# main.net
KiCad netlist of a schematic drawn in Altium Designer
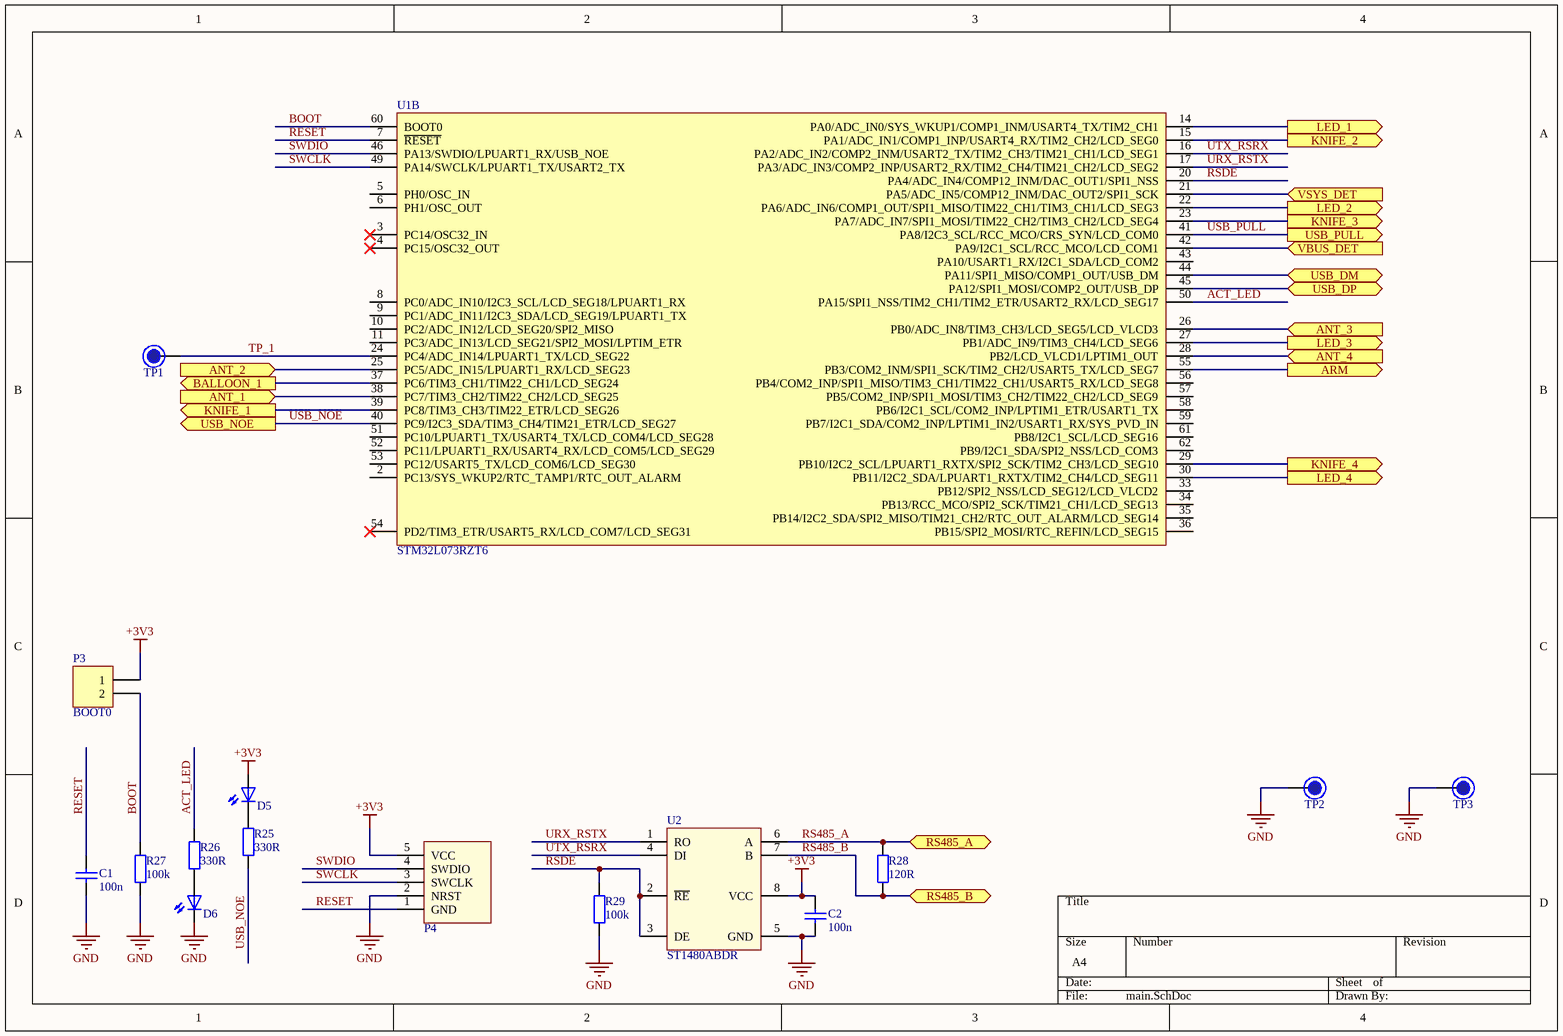
[diagram p0: main.SchDoc]

(export (version "E")
  (design (tool "Eeschema 10.0.6"))
  (components
    (comp (ref "C1")
      (value "100n")
      (footprint "C0603_IPC_MD")
      (description "CAP CER 0.1UF 16V X7R 0603")
      (fields
        (field (name "MANUFACTURER") "Samsung Electro-Mechanics")
        (field (name "MANUFACTURER PART NUMBER") "CL10B104KO8NNNC")
      )
      (libsource (lib "alfasat_lib") (part "CL10B104KO8NNNC"))
    )
    (comp (ref "C2")
      (value "100n")
      (footprint "C0603_IPC_MD")
      (description "CAP CER 0.1UF 16V X7R 0603")
      (fields
        (field (name "MANUFACTURER") "Samsung Electro-Mechanics")
        (field (name "MANUFACTURER PART NUMBER") "CL10B104KO8NNNC")
      )
      (libsource (lib "alfasat_lib") (part "CL10B104KO8NNNC"))
    )
    (comp (ref "D5")
      (value "LTST-C190GKT")
      (footprint "LED_0603")
      (description "LED GREEN CLEAR CHIP SMD 0603")
      (fields (field (name "MANUFACTURER") "Lite-On Inc."))
      (libsource (lib "alfasat_parts_lib") (part "LTST-C190GKT"))
    )
    (comp (ref "D6")
      (value "LTST-C190GKT")
      (footprint "LED_0603")
      (description "LED GREEN CLEAR CHIP SMD 0603")
      (fields (field (name "MANUFACTURER") "Lite-On Inc."))
      (libsource (lib "alfasat_lib") (part "LTST-C190GKT"))
    )
    (comp (ref "P3")
      (value "BOOT0")
      (footprint "HDR1X2")
      (description "Header, 2-Pin")
      (fields (field (name "PUBLISHER") "Altium Limited"))
      (libsource (lib "Miscellaneous Connectors") (part "Header 2"))
    )
    (comp (ref "P4")
      (value "SWD")
      (footprint "SWD_CON_VAR2")
      (description "SWDIO SWCLK VDD GND NRST")
      (libsource (lib "alfasat_lib") (part "SWD-CONNECTOR_VAR1"))
    )
    (comp (ref "R25")
      (value "330R")
      (footprint "R0603_IPC_MD")
      (description "RES SMD 330 OHM 5% 1/10W 0603")
      (fields
        (field (name "MANUFACTURER") "Bourns Inc.")
        (field (name "MANUFACTURER PART NUMBER") "CR0603-JW-331ELF")
      )
      (libsource (lib "alfasat_parts_lib") (part "CR0603-JW-331ELF"))
    )
    (comp (ref "R26")
      (value "330R")
      (footprint "R0603_IPC_MD")
      (description "RES SMD 330 OHM 5% 1/10W 0603")
      (fields
        (field (name "MANUFACTURER") "Bourns Inc.")
        (field (name "MANUFACTURER PART NUMBER") "CR0603-JW-331ELF")
      )
      (libsource (lib "alfasat_lib") (part "CR0603-JW-331ELF"))
    )
    (comp (ref "R27")
      (value "100k")
      (footprint "R0603_IPC_MD")
      (description "RES 100K OHM 1% 1/10W 0603")
      (fields
        (field (name "MANUFACTURER") "Bourns Inc.")
        (field (name "MANUFACTURER PART NUMBER") "RMCF0603FT100K")
      )
      (libsource (lib "alfasat_lib") (part "RMCF0603FT100K"))
    )
    (comp (ref "R28")
      (value "120R")
      (footprint "R0603_IPC_MD")
      (description "RES SMD 120 OHM 5% 1/10W 0603")
      (fields
        (field (name "MANUFACTURER") "Yageo")
        (field (name "MANUFACTURER PART NUMBER") "RC0603JR-07120RL")
      )
      (libsource (lib "alfasat_lib") (part "RC0603JR-07120RL"))
    )
    (comp (ref "R29")
      (value "100k")
      (footprint "R0603_IPC_MD")
      (description "RES 100K OHM 1% 1/10W 0603")
      (fields
        (field (name "MANUFACTURER") "Bourns Inc.")
        (field (name "MANUFACTURER PART NUMBER") "RMCF0603FT100K")
      )
      (libsource (lib "alfasat_lib") (part "RMCF0603FT100K"))
    )
    (comp (ref "TP1")
      (value "Test Point")
      (footprint "TestPoint_1M5")
      (libsource (lib "alfasat_parts_lib") (part "TP"))
    )
    (comp (ref "TP2")
      (value "GND")
      (footprint "TestPoint_1M5_TH")
      (description "Test Point")
      (libsource (lib "alfasat_parts_lib") (part "TP"))
    )
    (comp (ref "TP3")
      (value "GND")
      (footprint "TestPoint_1M5_TH")
      (description "Test Point")
      (libsource (lib "alfasat_parts_lib") (part "TP"))
    )
    (comp (ref "U1")
      (value "STM32L073RZT6")
      (footprint "LQFP64_10X10MM")
      (description "Ultra-low-power 32-bit MCU ARM®-based Cortex®-M0+")
      (fields (field (name "MANUFACTURER") "ST"))
      (libsource (lib "alfasat_parts_lib") (part "STM32L073RZT6"))
    )
    (comp (ref "U2")
      (value "ST1480ABDR")
      (footprint "SOIC-8")
      (description "IC TXRX 3.3V RS485/422 8 SOIC")
      (fields (field (name "MANUFACTURER") "STMicroelectronics"))
      (libsource (lib "alfasat_lib") (part "ST1480ABDR"))
    )
  )
  (nets
    (net (code "1") (name "+3V3") (class "Default")
      (node (ref "C2") (pin "2") (pinfunction "2_2") (pintype "passive"))
      (node (ref "D5") (pin "2") (pinfunction "A_2") (pintype "passive"))
      (node (ref "P3") (pin "1") (pinfunction "1_1") (pintype "passive"))
      (node (ref "P4") (pin "5") (pinfunction "VCC_5") (pintype "passive"))
      (node (ref "U2") (pin "8") (pinfunction "VCC_8") (pintype "passive"))
    )
    (net (code "2") (name "/ACT_LED") (class "Default")
      (node (ref "R26") (pin "1") (pinfunction "1_1") (pintype "passive"))
      (node (ref "U1") (pin "50") (pinfunction "PA15/SPI1_NSS/TIM2_CH1/TIM2_ETR/USART2_RX/LCD_SEG17_50") (pintype "passive"))
    )
    (net (code "3") (name "/ANT_1") (class "Default")
      (node (ref "U1") (pin "38") (pinfunction "PC7/TIM3_CH2/TIM22_CH2/LCD_SEG25_38") (pintype "passive"))
    )
    (net (code "4") (name "/ANT_2") (class "Default")
      (node (ref "U1") (pin "25") (pinfunction "PC5/ADC_IN15/LPUART1_RX/LCD_SEG23_25") (pintype "passive"))
    )
    (net (code "5") (name "/ANT_3") (class "Default")
      (node (ref "U1") (pin "26") (pinfunction "PB0/ADC_IN8/TIM3_CH3/LCD_SEG5/LCD_VLCD3_26") (pintype "passive"))
    )
    (net (code "6") (name "/ANT_4") (class "Default")
      (node (ref "U1") (pin "28") (pinfunction "PB2/LCD_VLCD1/LPTIM1_OUT_28") (pintype "passive"))
    )
    (net (code "7") (name "/ARM") (class "Default")
      (node (ref "U1") (pin "55") (pinfunction "PB3/COM2_INM/SPI1_SCK/TIM2_CH2/USART5_TX/LCD_SEG7_55") (pintype "passive"))
    )
    (net (code "8") (name "/BALLOON_1") (class "Default")
      (node (ref "U1") (pin "37") (pinfunction "PC6/TIM3_CH1/TIM22_CH1/LCD_SEG24_37") (pintype "passive"))
    )
    (net (code "9") (name "/BOOT") (class "Default")
      (node (ref "P3") (pin "2") (pinfunction "2_2") (pintype "passive"))
      (node (ref "R27") (pin "2") (pinfunction "2_2") (pintype "passive"))
      (node (ref "U1") (pin "60") (pinfunction "BOOT0_60") (pintype "passive"))
    )
    (net (code "10") (name "/KNIFE_1") (class "Default")
      (node (ref "U1") (pin "39") (pinfunction "PC8/TIM3_CH3/TIM22_ETR/LCD_SEG26_39") (pintype "passive"))
    )
    (net (code "11") (name "/KNIFE_2") (class "Default")
      (node (ref "U1") (pin "15") (pinfunction "PA1/ADC_IN1/COMP1_INP/USART4_RX/TIM2_CH2/LCD_SEG0_15") (pintype "passive"))
    )
    (net (code "12") (name "/KNIFE_3") (class "Default")
      (node (ref "U1") (pin "23") (pinfunction "PA7/ADC_IN7/SPI1_MOSI/TIM22_CH2/TIM3_CH2/LCD_SEG4_23") (pintype "passive"))
    )
    (net (code "13") (name "/KNIFE_4") (class "Default")
      (node (ref "U1") (pin "29") (pinfunction "PB10/I2C2_SCL/LPUART1_RXTX/SPI2_SCK/TIM2_CH3/LCD_SEG10_29") (pintype "passive"))
    )
    (net (code "14") (name "/LED_1") (class "Default")
      (node (ref "U1") (pin "14") (pinfunction "PA0/ADC_IN0/SYS_WKUP1/COMP1_INM/USART4_TX/TIM2_CH1_14") (pintype "passive"))
    )
    (net (code "15") (name "/LED_2") (class "Default")
      (node (ref "U1") (pin "22") (pinfunction "PA6/ADC_IN6/COMP1_OUT/SPI1_MISO/TIM22_CH1/TIM3_CH1/LCD_SEG3_22") (pintype "passive"))
    )
    (net (code "16") (name "/LED_3") (class "Default")
      (node (ref "U1") (pin "27") (pinfunction "PB1/ADC_IN9/TIM3_CH4/LCD_SEG6_27") (pintype "passive"))
    )
    (net (code "17") (name "/LED_4") (class "Default")
      (node (ref "U1") (pin "30") (pinfunction "PB11/I2C2_SDA/LPUART1_RXTX/TIM2_CH4/LCD_SEG11_30") (pintype "passive"))
    )
    (net (code "18") (name "/RESET") (class "Default")
      (node (ref "C1") (pin "2") (pinfunction "2_2") (pintype "passive"))
      (node (ref "P4") (pin "1") (pinfunction "GND_1") (pintype "passive"))
      (node (ref "U1") (pin "7") (pinfunction "~{RESET}_7") (pintype "passive"))
    )
    (net (code "19") (name "/RS485_A") (class "Default")
      (node (ref "R28") (pin "2") (pinfunction "2_2") (pintype "passive"))
      (node (ref "U2") (pin "6") (pinfunction "A_6") (pintype "passive"))
    )
    (net (code "20") (name "/RS485_B") (class "Default")
      (node (ref "R28") (pin "1") (pinfunction "1_1") (pintype "passive"))
      (node (ref "U2") (pin "7") (pinfunction "B_7") (pintype "passive"))
    )
    (net (code "21") (name "/RSDE") (class "Default")
      (node (ref "R29") (pin "2") (pinfunction "2_2") (pintype "passive"))
      (node (ref "U1") (pin "20") (pinfunction "PA4/ADC_IN4/COMP12_INM/DAC_OUT1/SPI1_NSS_20") (pintype "passive"))
      (node (ref "U2") (pin "2") (pinfunction "~{RE}_2") (pintype "passive"))
      (node (ref "U2") (pin "3") (pinfunction "DE_3") (pintype "passive"))
    )
    (net (code "22") (name "/SWCLK") (class "Default")
      (node (ref "P4") (pin "3") (pinfunction "SWCLK_3") (pintype "passive"))
      (node (ref "U1") (pin "49") (pinfunction "PA14/SWCLK/LPUART1_TX/USART2_TX_49") (pintype "passive"))
    )
    (net (code "23") (name "/SWDIO") (class "Default")
      (node (ref "P4") (pin "4") (pinfunction "SWDIO_4") (pintype "passive"))
      (node (ref "U1") (pin "46") (pinfunction "PA13/SWDIO/LPUART1_RX/USB_NOE_46") (pintype "passive"))
    )
    (net (code "24") (name "/TP_1") (class "Default")
      (node (ref "TP1") (pin "0") (pinfunction "0_0") (pintype "passive"))
      (node (ref "U1") (pin "24") (pinfunction "PC4/ADC_IN14/LPUART1_TX/LCD_SEG22_24") (pintype "passive"))
    )
    (net (code "25") (name "/URX_RSTX") (class "Default")
      (node (ref "U1") (pin "17") (pinfunction "PA3/ADC_IN3/COMP2_INP/USART2_RX/TIM2_CH4/TIM21_CH2/LCD_SEG2_17") (pintype "passive"))
      (node (ref "U2") (pin "1") (pinfunction "RO_1") (pintype "passive"))
    )
    (net (code "26") (name "/USB_DM") (class "Default")
      (node (ref "U1") (pin "44") (pinfunction "PA11/SPI1_MISO/COMP1_OUT/USB_DM_44") (pintype "passive"))
    )
    (net (code "27") (name "/USB_DP") (class "Default")
      (node (ref "U1") (pin "45") (pinfunction "PA12/SPI1_MOSI/COMP2_OUT/USB_DP_45") (pintype "passive"))
    )
    (net (code "28") (name "/USB_NOE") (class "Default")
      (node (ref "R25") (pin "2") (pinfunction "2_2") (pintype "passive"))
      (node (ref "U1") (pin "40") (pinfunction "PC9/I2C3_SDA/TIM3_CH4/TIM21_ETR/LCD_SEG27_40") (pintype "passive"))
    )
    (net (code "29") (name "/USB_PULL") (class "Default")
      (node (ref "U1") (pin "41") (pinfunction "PA8/I2C3_SCL/RCC_MCO/CRS_SYN/LCD_COM0_41") (pintype "passive"))
    )
    (net (code "30") (name "/UTX_RSRX") (class "Default")
      (node (ref "U1") (pin "16") (pinfunction "PA2/ADC_IN2/COMP2_INM/USART2_TX/TIM2_CH3/TIM21_CH1/LCD_SEG1_16") (pintype "passive"))
      (node (ref "U2") (pin "4") (pinfunction "DI_4") (pintype "passive"))
    )
    (net (code "31") (name "/VBUS_DET") (class "Default")
      (node (ref "U1") (pin "42") (pinfunction "PA9/I2C1_SCL/RCC_MCO/LCD_COM1_42") (pintype "passive"))
    )
    (net (code "32") (name "/VSYS_DET") (class "Default")
      (node (ref "U1") (pin "21") (pinfunction "PA5/ADC_IN5/COMP12_INM/DAC_OUT2/SPI1_SCK_21") (pintype "passive"))
    )
    (net (code "33") (name "GND") (class "Default")
      (node (ref "C1") (pin "1") (pinfunction "1_1") (pintype "passive"))
      (node (ref "C2") (pin "1") (pinfunction "1_1") (pintype "passive"))
      (node (ref "D6") (pin "1") (pinfunction "C_1") (pintype "passive"))
      (node (ref "P4") (pin "2") (pinfunction "NRST_2") (pintype "passive"))
      (node (ref "R27") (pin "1") (pinfunction "1_1") (pintype "passive"))
      (node (ref "R29") (pin "1") (pinfunction "1_1") (pintype "passive"))
      (node (ref "TP2") (pin "0") (pinfunction "0_0") (pintype "passive"))
      (node (ref "TP3") (pin "0") (pinfunction "0_0") (pintype "passive"))
      (node (ref "U2") (pin "5") (pinfunction "GND_5") (pintype "passive"))
    )
    (net (code "34") (name "Net-(D5-C)") (class "Default")
      (node (ref "D5") (pin "1") (pinfunction "C_1") (pintype "passive"))
      (node (ref "R25") (pin "1") (pinfunction "1_1") (pintype "passive"))
    )
    (net (code "35") (name "Net-(D6-A)") (class "Default")
      (node (ref "D6") (pin "2") (pinfunction "A_2") (pintype "passive"))
      (node (ref "R26") (pin "2") (pinfunction "2_2") (pintype "passive"))
    )
    (net (code "36") (name "unconnected-(U1B-PA10{slash}USART1_RX{slash}I2C1_SDA{slash}LCD_COM2-Pad43)") (class "Default")
      (node (ref "U1") (pin "43") (pinfunction "PA10/USART1_RX/I2C1_SDA/LCD_COM2_43") (pintype "passive"))
    )
    (net (code "37") (name "unconnected-(U1B-PB4{slash}COM2_INP{slash}SPI1_MISO{slash}TIM3_CH1{slash}TIM22_CH1{slash}USART5_RX{slash}LCD_SEG8-Pad56)") (class "Default")
      (node (ref "U1") (pin "56") (pinfunction "PB4/COM2_INP/SPI1_MISO/TIM3_CH1/TIM22_CH1/USART5_RX/LCD_SEG8_56") (pintype "passive"))
    )
    (net (code "38") (name "unconnected-(U1B-PB5{slash}COM2_INP{slash}SPI1_MOSI{slash}TIM3_CH2{slash}TIM22_CH2{slash}LCD_SEG9-Pad57)") (class "Default")
      (node (ref "U1") (pin "57") (pinfunction "PB5/COM2_INP/SPI1_MOSI/TIM3_CH2/TIM22_CH2/LCD_SEG9_57") (pintype "passive"))
    )
    (net (code "39") (name "unconnected-(U1B-PB6{slash}I2C1_SCL{slash}COM2_INP{slash}LPTIM1_ETR{slash}USART1_TX-Pad58)") (class "Default")
      (node (ref "U1") (pin "58") (pinfunction "PB6/I2C1_SCL/COM2_INP/LPTIM1_ETR/USART1_TX_58") (pintype "passive"))
    )
    (net (code "40") (name "unconnected-(U1B-PB7{slash}I2C1_SDA{slash}COM2_INP{slash}LPTIM1_IN2{slash}USART1_RX{slash}SYS_PVD_IN-Pad59)") (class "Default")
      (node (ref "U1") (pin "59") (pinfunction "PB7/I2C1_SDA/COM2_INP/LPTIM1_IN2/USART1_RX/SYS_PVD_IN_59") (pintype "passive"))
    )
    (net (code "41") (name "unconnected-(U1B-PB8{slash}I2C1_SCL{slash}LCD_SEG16-Pad61)") (class "Default")
      (node (ref "U1") (pin "61") (pinfunction "PB8/I2C1_SCL/LCD_SEG16_61") (pintype "passive"))
    )
    (net (code "42") (name "unconnected-(U1B-PB9{slash}I2C1_SDA{slash}SPI2_NSS{slash}LCD_COM3-Pad62)") (class "Default")
      (node (ref "U1") (pin "62") (pinfunction "PB9/I2C1_SDA/SPI2_NSS/LCD_COM3_62") (pintype "passive"))
    )
    (net (code "43") (name "unconnected-(U1B-PB12{slash}SPI2_NSS{slash}LCD_SEG12{slash}LCD_VLCD2-Pad33)") (class "Default")
      (node (ref "U1") (pin "33") (pinfunction "PB12/SPI2_NSS/LCD_SEG12/LCD_VLCD2_33") (pintype "passive"))
    )
    (net (code "44") (name "unconnected-(U1B-PB13{slash}RCC_MCO{slash}SPI2_SCK{slash}TIM21_CH1{slash}LCD_SEG13-Pad34)") (class "Default")
      (node (ref "U1") (pin "34") (pinfunction "PB13/RCC_MCO/SPI2_SCK/TIM21_CH1/LCD_SEG13_34") (pintype "passive"))
    )
    (net (code "45") (name "unconnected-(U1B-PB14{slash}I2C2_SDA{slash}SPI2_MISO{slash}TIM21_CH2{slash}RTC_OUT_ALARM{slash}LCD_SEG14-Pad35)") (class "Default")
      (node (ref "U1") (pin "35") (pinfunction "PB14/I2C2_SDA/SPI2_MISO/TIM21_CH2/RTC_OUT_ALARM/LCD_SEG14_35") (pintype "passive"))
    )
    (net (code "46") (name "unconnected-(U1B-PB15{slash}SPI2_MOSI{slash}RTC_REFIN{slash}LCD_SEG15-Pad36)") (class "Default")
      (node (ref "U1") (pin "36") (pinfunction "PB15/SPI2_MOSI/RTC_REFIN/LCD_SEG15_36") (pintype "passive"))
    )
    (net (code "47") (name "unconnected-(U1B-PC0{slash}ADC_IN10{slash}I2C3_SCL{slash}LCD_SEG18{slash}LPUART1_RX-Pad8)") (class "Default")
      (node (ref "U1") (pin "8") (pinfunction "PC0/ADC_IN10/I2C3_SCL/LCD_SEG18/LPUART1_RX_8") (pintype "passive"))
    )
    (net (code "48") (name "unconnected-(U1B-PC1{slash}ADC_IN11{slash}I2C3_SDA{slash}LCD_SEG19{slash}LPUART1_TX-Pad9)") (class "Default")
      (node (ref "U1") (pin "9") (pinfunction "PC1/ADC_IN11/I2C3_SDA/LCD_SEG19/LPUART1_TX_9") (pintype "passive"))
    )
    (net (code "49") (name "unconnected-(U1B-PC2{slash}ADC_IN12{slash}LCD_SEG20{slash}SPI2_MISO-Pad10)") (class "Default")
      (node (ref "U1") (pin "10") (pinfunction "PC2/ADC_IN12/LCD_SEG20/SPI2_MISO_10") (pintype "passive"))
    )
    (net (code "50") (name "unconnected-(U1B-PC3{slash}ADC_IN13{slash}LCD_SEG21{slash}SPI2_MOSI{slash}LPTIM_ETR-Pad11)") (class "Default")
      (node (ref "U1") (pin "11") (pinfunction "PC3/ADC_IN13/LCD_SEG21/SPI2_MOSI/LPTIM_ETR_11") (pintype "passive"))
    )
    (net (code "51") (name "unconnected-(U1B-PC10{slash}LPUART1_TX{slash}USART4_TX{slash}LCD_COM4{slash}LCD_SEG28-Pad51)") (class "Default")
      (node (ref "U1") (pin "51") (pinfunction "PC10/LPUART1_TX/USART4_TX/LCD_COM4/LCD_SEG28_51") (pintype "passive"))
    )
    (net (code "52") (name "unconnected-(U1B-PC11{slash}LPUART1_RX{slash}USART4_RX{slash}LCD_COM5{slash}LCD_SEG29-Pad52)") (class "Default")
      (node (ref "U1") (pin "52") (pinfunction "PC11/LPUART1_RX/USART4_RX/LCD_COM5/LCD_SEG29_52") (pintype "passive"))
    )
    (net (code "53") (name "unconnected-(U1B-PC12{slash}USART5_TX{slash}LCD_COM6{slash}LCD_SEG30-Pad53)") (class "Default")
      (node (ref "U1") (pin "53") (pinfunction "PC12/USART5_TX/LCD_COM6/LCD_SEG30_53") (pintype "passive"))
    )
    (net (code "54") (name "unconnected-(U1B-PC13{slash}SYS_WKUP2{slash}RTC_TAMP1{slash}RTC_OUT_ALARM-Pad2)") (class "Default")
      (node (ref "U1") (pin "2") (pinfunction "PC13/SYS_WKUP2/RTC_TAMP1/RTC_OUT_ALARM_2") (pintype "passive"))
    )
    (net (code "55") (name "unconnected-(U1B-PC14{slash}OSC32_IN-Pad3)") (class "Default")
      (node (ref "U1") (pin "3") (pinfunction "PC14/OSC32_IN_3") (pintype "passive+no_connect"))
    )
    (net (code "56") (name "unconnected-(U1B-PC15{slash}OSC32_OUT-Pad4)") (class "Default")
      (node (ref "U1") (pin "4") (pinfunction "PC15/OSC32_OUT_4") (pintype "passive+no_connect"))
    )
    (net (code "57") (name "unconnected-(U1B-PD2{slash}TIM3_ETR{slash}USART5_RX{slash}LCD_COM7{slash}LCD_SEG31-Pad54)") (class "Default")
      (node (ref "U1") (pin "54") (pinfunction "PD2/TIM3_ETR/USART5_RX/LCD_COM7/LCD_SEG31_54") (pintype "passive+no_connect"))
    )
    (net (code "58") (name "unconnected-(U1B-PH0{slash}OSC_IN-Pad5)") (class "Default")
      (node (ref "U1") (pin "5") (pinfunction "PH0/OSC_IN_5") (pintype "passive"))
    )
    (net (code "59") (name "unconnected-(U1B-PH1{slash}OSC_OUT-Pad6)") (class "Default")
      (node (ref "U1") (pin "6") (pinfunction "PH1/OSC_OUT_6") (pintype "passive"))
    )
  )
)
